# Geiger_Counter_II_2021-02-28.net
KiCad netlist of a schematic drawn in EasyEDA
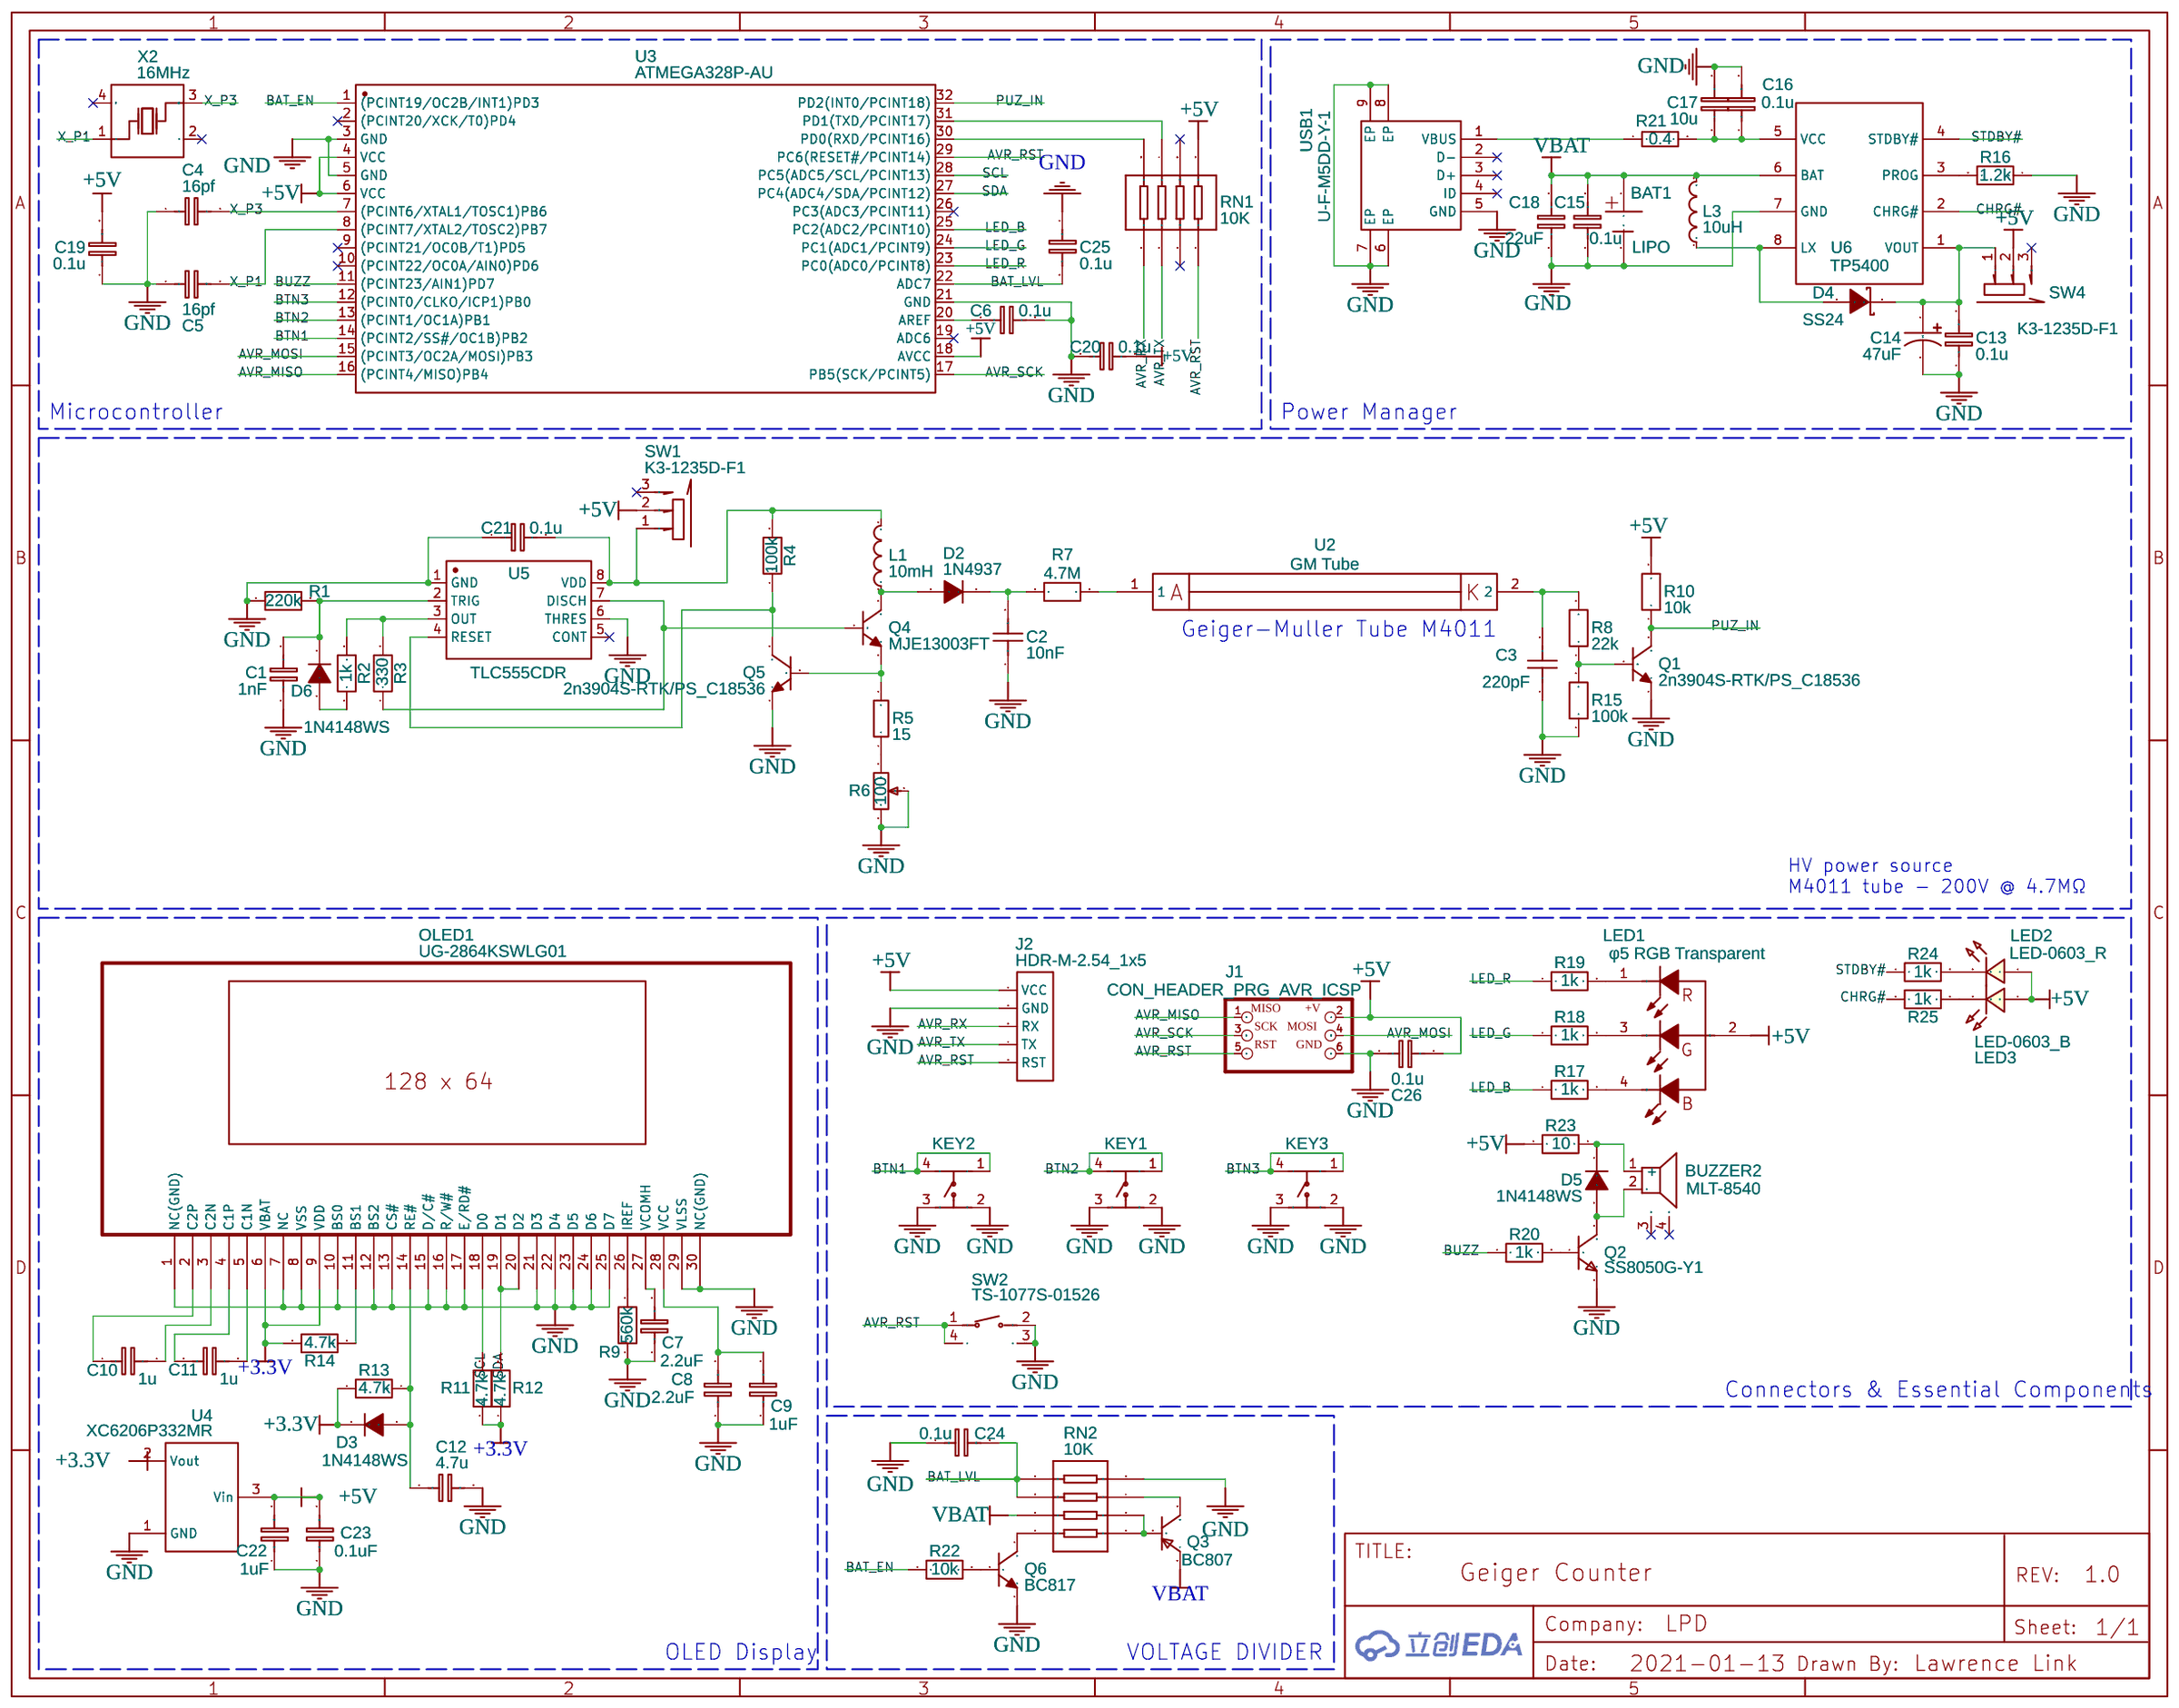
[diagram p0: schematic sheet]

(export (version "E")
  (design (tool "Eeschema 10.0.6"))
  (components
    (comp (ref "BAT1")
      (value "LIPO")
      (fields (field (name "BOM_Supplier Part") "C426276"))
      (libsource (lib "") (part "Lithum-Polymer"))
    )
    (comp (ref "BUZZER2")
      (value "MLT-8540")
      (fields (field (name "BOM_Supplier Part") "C95300"))
      (libsource (lib "") (part "MLT-8540"))
    )
    (comp (ref "C1") (value "1nF") (libsource (lib "") (part "C_0603_EU_9")))
    (comp (ref "C2")
      (value "10nF")
      (fields
        (field (name "BOM_Manufacturer Part") "KP103J2J0701")
        (field (name "BOM_Supplier Part") "C390071")
      )
      (libsource (lib "") (part "KP103J2J0701"))
    )
    (comp (ref "C3")
      (value "220pF")
      (fields
        (field (name "BOM_Manufacturer Part") "FM31X221K501ECG")
        (field (name "BOM_Supplier Part") "C382231")
      )
      (libsource (lib "") (part "FM31X221K501ECG"))
    )
    (comp (ref "C4") (value "16pf") (libsource (lib "") (part "C_0603_EU_1")))
    (comp (ref "C5") (value "16pf") (libsource (lib "") (part "C_0603_EU_11")))
    (comp (ref "C6") (value "0.1u") (libsource (lib "") (part "C_0603_EU_1")))
    (comp (ref "C7") (value "2.2uF") (libsource (lib "") (part "C_0603_EU_4")))
    (comp (ref "C8") (value "2.2uF") (libsource (lib "") (part "C_0603_EU_4")))
    (comp (ref "C9") (value "1uF") (libsource (lib "") (part "C_0603_EU_4")))
    (comp (ref "C10") (value "1u") (libsource (lib "") (part "C_0603_EU_3")))
    (comp (ref "C11") (value "1u") (libsource (lib "") (part "C_0603_EU_3")))
    (comp (ref "C12") (value "4.7u") (libsource (lib "") (part "C_0603_EU_7")))
    (comp (ref "C13") (value "0.1u") (libsource (lib "") (part "C_0603_EU")))
    (comp (ref "C14")
      (value "47uF")
      (fields
        (field (name "BOM_Manufacturer Part") "F920J476MBA")
        (field (name "BOM_Supplier Part") "C389937")
      )
      (libsource (lib "") (part "F920J476MBA"))
    )
    (comp (ref "C15") (value "0.1u") (libsource (lib "") (part "C_0603_EU")))
    (comp (ref "C16") (value "0.1u") (libsource (lib "") (part "C_0603_EU")))
    (comp (ref "C17") (value "10u") (libsource (lib "") (part "C_0603_EU_2")))
    (comp (ref "C18") (value "22uF") (libsource (lib "") (part "C_0603_EU")))
    (comp (ref "C19") (value "0.1u") (libsource (lib "") (part "C_0603_EU_2")))
    (comp (ref "C20") (value "0.1u") (libsource (lib "") (part "C_0603_EU_1")))
    (comp (ref "C21") (value "0.1u") (libsource (lib "") (part "C_0603_EU_8")))
    (comp (ref "C22") (value "1uF") (libsource (lib "") (part "C_0603_EU_10")))
    (comp (ref "C23") (value "0.1uF") (libsource (lib "") (part "C_0603_EU_10")))
    (comp (ref "C24") (value "0.1u") (libsource (lib "") (part "C_0603_EU_3")))
    (comp (ref "C25") (value "0.1u") (libsource (lib "") (part "C_0603_EU_5")))
    (comp (ref "C26") (value "0.1u") (libsource (lib "") (part "C_0603_EU_6")))
    (comp (ref "D2")
      (value "1N4937")
      (fields (field (name "BOM_Supplier Part") "C237246"))
      (libsource (lib "") (part "1N4937"))
    )
    (comp (ref "D3")
      (value "1N4148WS")
      (fields (field (name "BOM_Supplier Part") "C179718"))
      (libsource (lib "") (part "1N4148WS_1"))
    )
    (comp (ref "D4")
      (value "SS24")
      (fields (field (name "BOM_Supplier Part") "C50645"))
      (libsource (lib "") (part "SS24"))
    )
    (comp (ref "D5")
      (value "1N4148WS")
      (fields (field (name "BOM_Supplier Part") "C179718"))
      (libsource (lib "") (part "1N4148WS"))
    )
    (comp (ref "D6")
      (value "1N4148WS")
      (fields (field (name "BOM_Supplier Part") "C179718"))
      (libsource (lib "") (part "1N4148WS"))
    )
    (comp (ref "J1") (value "CON_HEADER_PRG_AVR_ICSP") (libsource (lib "") (part "CON_HEADER_PRG_AVR_ICSP")))
    (comp (ref "J2")
      (value "HDR-M-2.54_1x5")
      (fields (field (name "BOM_Supplier Part") "C358687"))
      (libsource (lib "") (part "HDR-M-2.54_1x5"))
    )
    (comp (ref "KEY1")
      (value "TL3301NF160QG/P010515")
      (fields (field (name "BOM_Supplier Part") "C273527"))
      (libsource (lib "") (part "TL3301NF160QG/P010515"))
    )
    (comp (ref "KEY2")
      (value "TL3301NF160QG/P010515")
      (fields (field (name "BOM_Supplier Part") "C273527"))
      (libsource (lib "") (part "TL3301NF160QG/P010515"))
    )
    (comp (ref "KEY3")
      (value "TL3301NF160QG/P010515")
      (fields (field (name "BOM_Supplier Part") "C273527"))
      (libsource (lib "") (part "TL3301NF160QG/P010515"))
    )
    (comp (ref "L1")
      (value "10mH")
      (fields
        (field (name "BOM_Manufacturer Part") "FNR6045S103KT")
        (field (name "BOM_Supplier Part") "C168108")
      )
      (libsource (lib "") (part "FNR6045S103KT"))
    )
    (comp (ref "L3")
      (value "10uH")
      (fields
        (field (name "BOM_Manufacturer Part") "CKCS6045-10uH/M")
        (field (name "BOM_Supplier Part") "C354632")
      )
      (libsource (lib "") (part "CKCS6045-10UH/M"))
    )
    (comp (ref "LED1")
      (value "φ5 RGB Transparent")
      (fields
        (field (name "BOM_Manufacturer Part") "φ5 RGB Transparent LED")
        (field (name "BOM_Supplier Part") "C32985")
      )
      (libsource (lib "") (part "φ5 RGB Transparent"))
    )
    (comp (ref "LED2")
      (value "LED-0603_R")
      (fields
        (field (name "BOM_Manufacturer Part") "19-217/R6C-AL1M2VY/3T")
        (field (name "BOM_Supplier Part") "C72044")
      )
      (libsource (lib "") (part "LED-0603_R"))
    )
    (comp (ref "LED3")
      (value "LED-0603_B")
      (fields
        (field (name "BOM_Manufacturer Part") "19-217/BHC-ZL1M2RY/3T")
        (field (name "BOM_Supplier Part") "C72041")
      )
      (libsource (lib "") (part "LED-0603_B"))
    )
    (comp (ref "OLED1")
      (value "UG-2864KSWLG01")
      (fields (field (name "BOM_Supplier Part") "C113322"))
      (libsource (lib "") (part "UG-2864KSWLG01"))
    )
    (comp (ref "Q1")
      (value "2n3904S-RTK/PS_C18536")
      (fields
        (field (name "BOM_Manufacturer Part") "2n3904S-RTK/PS")
        (field (name "BOM_Supplier Part") "C18536")
      )
      (libsource (lib "") (part "2n3904S-RTK/PS_C18536"))
    )
    (comp (ref "Q2")
      (value "SS8050G-Y1")
      (fields (field (name "BOM_Supplier Part") "C380930"))
      (libsource (lib "") (part "SS8050G-Y1"))
    )
    (comp (ref "Q3")
      (value "BC807")
      (fields (field (name "BOM_Supplier Part") "C466642"))
      (libsource (lib "") (part "BC807"))
    )
    (comp (ref "Q4")
      (value "MJE13003FT")
      (fields (field (name "BOM_Supplier Part") "C358520"))
      (libsource (lib "") (part "MJE13003FT"))
    )
    (comp (ref "Q5")
      (value "2n3904S-RTK/PS_C18536")
      (fields
        (field (name "BOM_Manufacturer Part") "2n3904S-RTK/PS")
        (field (name "BOM_Supplier Part") "C18536")
      )
      (libsource (lib "") (part "2n3904S-RTK/PS_C18536_1"))
    )
    (comp (ref "Q6")
      (value "BC817")
      (fields (field (name "BOM_Supplier Part") "C8589"))
      (libsource (lib "") (part "BC817"))
    )
    (comp (ref "R1") (value "220k") (libsource (lib "") (part "R_0603_EU")))
    (comp (ref "R2") (value "1k") (libsource (lib "") (part "R_0603_EU_1")))
    (comp (ref "R3") (value "330") (libsource (lib "") (part "R_0603_EU_1")))
    (comp (ref "R4") (value "100k") (libsource (lib "") (part "R_0603_EU_1")))
    (comp (ref "R5")
      (value "15")
      (fields
        (field (name "BOM_Manufacturer Part") "AR06BTDV0150")
        (field (name "BOM_Supplier Part") "C319834")
      )
      (libsource (lib "") (part "AR06BTDV0150"))
    )
    (comp (ref "R6")
      (value "100")
      (fields
        (field (name "BOM_Manufacturer Part") "3386P-1-101LF")
        (field (name "BOM_Supplier Part") "C125022")
      )
      (libsource (lib "") (part "3386P-1-101LF_EU"))
    )
    (comp (ref "R7") (value "4.7M") (libsource (lib "") (part "R_AXIAL-0.3_EU")))
    (comp (ref "R8") (value "22k") (libsource (lib "") (part "R_0805_EU_1")))
    (comp (ref "R9") (value "560k") (libsource (lib "") (part "R_0603_EU_1")))
    (comp (ref "R10") (value "10k") (libsource (lib "") (part "R_0805_EU_1")))
    (comp (ref "R11") (value "4.7k") (libsource (lib "") (part "R_0603_EU_1")))
    (comp (ref "R12") (value "4.7k") (libsource (lib "") (part "R_0603_EU_1")))
    (comp (ref "R13") (value "4.7k") (libsource (lib "") (part "R_0603_EU")))
    (comp (ref "R14") (value "4.7k") (libsource (lib "") (part "R_0603_EU_2")))
    (comp (ref "R15") (value "100k") (libsource (lib "") (part "R_0805_EU_1")))
    (comp (ref "R16") (value "1.2k") (libsource (lib "") (part "R_0603_EU")))
    (comp (ref "R17") (value "1k") (libsource (lib "") (part "R_0805_EU")))
    (comp (ref "R18") (value "1k") (libsource (lib "") (part "R_0805_EU")))
    (comp (ref "R19") (value "1k") (libsource (lib "") (part "R_0805_EU")))
    (comp (ref "R20") (value "1k") (libsource (lib "") (part "R_0603_EU_2")))
    (comp (ref "R21")
      (value "0.4")
      (fields
        (field (name "BOM_Manufacturer Part") "1206W4J040KT5E")
        (field (name "BOM_Supplier Part") "C620968")
      )
      (libsource (lib "") (part "1206W4J040KT5E"))
    )
    (comp (ref "R22") (value "10k") (libsource (lib "") (part "R_0603_EU_2")))
    (comp (ref "R23") (value "10") (libsource (lib "") (part "R_0603_EU_2")))
    (comp (ref "R24") (value "1k") (libsource (lib "") (part "R_0603_EU_2")))
    (comp (ref "R25") (value "1k") (libsource (lib "") (part "R_0603_EU_2")))
    (comp (ref "RN1")
      (value "10K")
      (fields
        (field (name "BOM_Manufacturer Part") "CN34JTN102")
        (field (name "BOM_Supplier Part") "C153136")
      )
      (libsource (lib "") (part "CN34JTN102"))
    )
    (comp (ref "RN2")
      (value "10K")
      (fields
        (field (name "BOM_Manufacturer Part") "4D03WGJ0103T5E")
        (field (name "BOM_Supplier Part") "C29718")
      )
      (libsource (lib "") (part "4D03WGJ0103T5E"))
    )
    (comp (ref "SW1")
      (value "K3-1235D-F1")
      (fields (field (name "BOM_Supplier Part") "C223839"))
      (libsource (lib "") (part "K3-1235D-F1"))
    )
    (comp (ref "SW2")
      (value "TS-1077S-01526")
      (fields (field (name "BOM_Supplier Part") "C455259"))
      (libsource (lib "") (part "TS-1077S-01526"))
    )
    (comp (ref "SW4")
      (value "K3-1235D-F1")
      (fields (field (name "BOM_Supplier Part") "C223839"))
      (libsource (lib "") (part "K3-1235D-F1_1"))
    )
    (comp (ref "U2") (value "GM Tube") (libsource (lib "") (part "GM Tube")))
    (comp (ref "U3")
      (value "ATMEGA328P-AU")
      (fields (field (name "BOM_Supplier Part") "C14877"))
      (libsource (lib "") (part "ATMEGA328P-AU"))
    )
    (comp (ref "U4")
      (value "XC6206P332MR")
      (fields (field (name "BOM_Supplier Part") "C5446"))
      (libsource (lib "") (part "XC6206P332MR"))
    )
    (comp (ref "U5")
      (value "TLC555CDR")
      (fields (field (name "BOM_Supplier Part") "C6986"))
      (libsource (lib "") (part "TLC555CDR"))
    )
    (comp (ref "U6")
      (value "TP5400")
      (fields (field (name "BOM_Supplier Part") "C24154"))
      (libsource (lib "") (part "TP5400"))
    )
    (comp (ref "USB1")
      (value "U-F-M5DD-Y-1")
      (fields (field (name "BOM_Supplier Part") "C91467"))
      (libsource (lib "") (part "U-F-M5DD-Y-1"))
    )
    (comp (ref "X2")
      (value "16MHz")
      (fields (field (name "BOM_Supplier Part") "C164049"))
      (libsource (lib "") (part "SMD-3225_4P 16MHz 20pF 10ppm -40&#126;+85℃"))
    )
  )
  (nets
    (net (code "1") (name "+3.3V") (class "Default")
      (node (ref "D3") (pin "1") (pinfunction "K_1") (pintype "unspecified"))
      (node (ref "OLED1") (pin "6") (pinfunction "VBAT_6") (pintype "passive"))
      (node (ref "OLED1") (pin "9") (pinfunction "VDD_9") (pintype "passive"))
      (node (ref "R11") (pin "1") (pinfunction "1_1") (pintype "unspecified"))
      (node (ref "R12") (pin "1") (pinfunction "1_1") (pintype "unspecified"))
      (node (ref "R13") (pin "2") (pinfunction "2_2") (pintype "unspecified"))
      (node (ref "R14") (pin "1") (pinfunction "1_1") (pintype "unspecified"))
      (node (ref "U4") (pin "2") (pinfunction "Vout_2") (pintype "unspecified"))
    )
    (net (code "2") (name "+5V") (class "Default")
      (node (ref "C19") (pin "2") (pinfunction "2_2") (pintype "unspecified"))
      (node (ref "C20") (pin "2") (pinfunction "2_2") (pintype "unspecified"))
      (node (ref "C22") (pin "2") (pinfunction "2_2") (pintype "unspecified"))
      (node (ref "C23") (pin "2") (pinfunction "2_2") (pintype "unspecified"))
      (node (ref "C26") (pin "2") (pinfunction "2_2") (pintype "unspecified"))
      (node (ref "J1") (pin "2") (pinfunction "+V_2") (pintype "unspecified"))
      (node (ref "J2") (pin "1") (pinfunction "VCC_1") (pintype "unspecified"))
      (node (ref "LED1") (pin "2") (pinfunction "CA_2") (pintype "unspecified"))
      (node (ref "LED2") (pin "1") (pinfunction "1_1") (pintype "unspecified"))
      (node (ref "LED3") (pin "1") (pinfunction "1_1") (pintype "unspecified"))
      (node (ref "R10") (pin "2") (pinfunction "2_2") (pintype "unspecified"))
      (node (ref "R23") (pin "1") (pinfunction "1_1") (pintype "unspecified"))
      (node (ref "RN1") (pin "5") (pinfunction "5_5") (pintype "input"))
      (node (ref "SW1") (pin "2") (pinfunction "2_2") (pintype "unspecified"))
      (node (ref "SW4") (pin "2") (pinfunction "2_2") (pintype "unspecified"))
      (node (ref "U3") (pin "18") (pinfunction "AVCC_18") (pintype "unspecified"))
      (node (ref "U3") (pin "4") (pinfunction "VCC_4") (pintype "unspecified"))
      (node (ref "U3") (pin "6") (pinfunction "VCC_6") (pintype "unspecified"))
      (node (ref "U4") (pin "3") (pinfunction "Vin_3") (pintype "unspecified"))
    )
    (net (code "3") (name "/AVR_MISO") (class "Default")
      (node (ref "J1") (pin "1") (pinfunction "MISO_1") (pintype "unspecified"))
      (node (ref "U3") (pin "16") (pinfunction "(PCINT4/MISO)PB4_16") (pintype "unspecified"))
    )
    (net (code "4") (name "/AVR_MOSI") (class "Default")
      (node (ref "J1") (pin "4") (pinfunction "MOSI_4") (pintype "unspecified"))
      (node (ref "U3") (pin "15") (pinfunction "(PCINT3/OC2A/MOSI)PB3_15") (pintype "unspecified"))
    )
    (net (code "5") (name "/AVR_RST") (class "Default")
      (node (ref "J1") (pin "5") (pinfunction "RST_5") (pintype "unspecified"))
      (node (ref "J2") (pin "5") (pinfunction "RST_5") (pintype "unspecified"))
      (node (ref "RN1") (pin "4") (pinfunction "4_4") (pintype "input"))
      (node (ref "SW2") (pin "1") (pinfunction "1_1") (pintype "unspecified"))
      (node (ref "SW2") (pin "4") (pinfunction "4_4") (pintype "unspecified"))
      (node (ref "U3") (pin "29") (pinfunction "PC6(RESET#/PCINT14)_29") (pintype "unspecified"))
    )
    (net (code "6") (name "/AVR_RX") (class "Default")
      (node (ref "J2") (pin "3") (pinfunction "RX_3") (pintype "unspecified"))
      (node (ref "RN1") (pin "1") (pinfunction "1_1") (pintype "input"))
    )
    (net (code "7") (name "/AVR_SCK") (class "Default")
      (node (ref "J1") (pin "3") (pinfunction "SCK_3") (pintype "unspecified"))
      (node (ref "U3") (pin "17") (pinfunction "PB5(SCK/PCINT5)_17") (pintype "unspecified"))
    )
    (net (code "8") (name "/AVR_TX") (class "Default")
      (node (ref "J2") (pin "4") (pinfunction "TX_4") (pintype "unspecified"))
      (node (ref "RN1") (pin "2") (pinfunction "2_2") (pintype "input"))
    )
    (net (code "9") (name "/BAT_EN") (class "Default")
      (node (ref "R22") (pin "1") (pinfunction "1_1") (pintype "unspecified"))
      (node (ref "U3") (pin "1") (pinfunction "(PCINT19/OC2B/INT1)PD3_1") (pintype "unspecified"))
    )
    (net (code "10") (name "/BAT_LVL") (class "Default")
      (node (ref "C24") (pin "2") (pinfunction "2_2") (pintype "unspecified"))
      (node (ref "C25") (pin "2") (pinfunction "2_2") (pintype "unspecified"))
      (node (ref "RN2") (pin "1") (pinfunction "1_1") (pintype "input"))
      (node (ref "RN2") (pin "2") (pinfunction "2_2") (pintype "input"))
      (node (ref "U3") (pin "22") (pinfunction "ADC7_22") (pintype "unspecified"))
    )
    (net (code "11") (name "/BTN1") (class "Default")
      (node (ref "KEY2") (pin "1") (pinfunction "3_1") (pintype "unspecified"))
      (node (ref "KEY2") (pin "4") (pinfunction "4_4") (pintype "unspecified"))
      (node (ref "U3") (pin "14") (pinfunction "(PCINT2/SS#/OC1B)PB2_14") (pintype "unspecified"))
    )
    (net (code "12") (name "/BTN2") (class "Default")
      (node (ref "KEY1") (pin "1") (pinfunction "3_1") (pintype "unspecified"))
      (node (ref "KEY1") (pin "4") (pinfunction "4_4") (pintype "unspecified"))
      (node (ref "U3") (pin "13") (pinfunction "(PCINT1/OC1A)PB1_13") (pintype "unspecified"))
    )
    (net (code "13") (name "/BTN3") (class "Default")
      (node (ref "KEY3") (pin "1") (pinfunction "3_1") (pintype "unspecified"))
      (node (ref "KEY3") (pin "4") (pinfunction "4_4") (pintype "unspecified"))
      (node (ref "U3") (pin "12") (pinfunction "(PCINT0/CLKO/ICP1)PB0_12") (pintype "unspecified"))
    )
    (net (code "14") (name "/BUZZ") (class "Default")
      (node (ref "R20") (pin "1") (pinfunction "1_1") (pintype "unspecified"))
      (node (ref "U3") (pin "11") (pinfunction "(PCINT23/AIN1)PD7_11") (pintype "unspecified"))
    )
    (net (code "15") (name "/CHRG#") (class "Default")
      (node (ref "R25") (pin "1") (pinfunction "1_1") (pintype "unspecified"))
      (node (ref "U6") (pin "2") (pinfunction "CHRG#_2") (pintype "unspecified"))
    )
    (net (code "16") (name "/LED_B") (class "Default")
      (node (ref "R17") (pin "1") (pinfunction "1_1") (pintype "unspecified"))
      (node (ref "U3") (pin "25") (pinfunction "PC2(ADC2/PCINT10)_25") (pintype "unspecified"))
    )
    (net (code "17") (name "/LED_G") (class "Default")
      (node (ref "R18") (pin "1") (pinfunction "1_1") (pintype "unspecified"))
      (node (ref "U3") (pin "24") (pinfunction "PC1(ADC1/PCINT9)_24") (pintype "unspecified"))
    )
    (net (code "18") (name "/LED_R") (class "Default")
      (node (ref "R19") (pin "1") (pinfunction "1_1") (pintype "unspecified"))
      (node (ref "U3") (pin "23") (pinfunction "PC0(ADC0/PCINT8)_23") (pintype "unspecified"))
    )
    (net (code "19") (name "/PUZ_IN") (class "Default")
      (node (ref "Q1") (pin "3") (pinfunction "C_3") (pintype "input"))
      (node (ref "R10") (pin "1") (pinfunction "1_1") (pintype "unspecified"))
      (node (ref "U3") (pin "32") (pinfunction "PD2(INT0/PCINT18)_32") (pintype "unspecified"))
    )
    (net (code "20") (name "/SCL") (class "Default")
      (node (ref "OLED1") (pin "18") (pinfunction "D0_18") (pintype "passive"))
      (node (ref "R11") (pin "2") (pinfunction "2_2") (pintype "unspecified"))
      (node (ref "U3") (pin "28") (pinfunction "PC5(ADC5/SCL/PCINT13)_28") (pintype "unspecified"))
    )
    (net (code "21") (name "/SDA") (class "Default")
      (node (ref "OLED1") (pin "19") (pinfunction "D1_19") (pintype "passive"))
      (node (ref "OLED1") (pin "20") (pinfunction "D2_20") (pintype "passive"))
      (node (ref "R12") (pin "2") (pinfunction "2_2") (pintype "unspecified"))
      (node (ref "U3") (pin "27") (pinfunction "PC4(ADC4/SDA/PCINT12)_27") (pintype "unspecified"))
    )
    (net (code "22") (name "/STDBY#") (class "Default")
      (node (ref "R24") (pin "1") (pinfunction "1_1") (pintype "unspecified"))
      (node (ref "U6") (pin "4") (pinfunction "STDBY#_4") (pintype "unspecified"))
    )
    (net (code "23") (name "/X_P1") (class "Default")
      (node (ref "C5") (pin "2") (pinfunction "2_2") (pintype "unspecified"))
      (node (ref "U3") (pin "8") (pinfunction "(PCINT7/XTAL2/TOSC2)PB7_8") (pintype "unspecified"))
      (node (ref "X2") (pin "1") (pinfunction "OSC1_1") (pintype "unspecified"))
    )
    (net (code "24") (name "/X_P3") (class "Default")
      (node (ref "C4") (pin "2") (pinfunction "2_2") (pintype "unspecified"))
      (node (ref "U3") (pin "7") (pinfunction "(PCINT6/XTAL1/TOSC1)PB6_7") (pintype "unspecified"))
      (node (ref "X2") (pin "3") (pinfunction "OSC2_3") (pintype "unspecified"))
    )
    (net (code "25") (name "GND") (class "Default")
      (node (ref "BAT1") (pin "2") (pinfunction "2_2") (pintype "unspecified"))
      (node (ref "C1") (pin "1") (pinfunction "1_1") (pintype "unspecified"))
      (node (ref "C12") (pin "2") (pinfunction "2_2") (pintype "unspecified"))
      (node (ref "C13") (pin "1") (pinfunction "1_1") (pintype "unspecified"))
      (node (ref "C14") (pin "2") (pinfunction "2_2") (pintype "unspecified"))
      (node (ref "C15") (pin "1") (pinfunction "1_1") (pintype "unspecified"))
      (node (ref "C16") (pin "2") (pinfunction "2_2") (pintype "unspecified"))
      (node (ref "C17") (pin "2") (pinfunction "2_2") (pintype "unspecified"))
      (node (ref "C18") (pin "1") (pinfunction "1_1") (pintype "unspecified"))
      (node (ref "C19") (pin "1") (pinfunction "1_1") (pintype "unspecified"))
      (node (ref "C2") (pin "1") (pinfunction "1_1") (pintype "unspecified"))
      (node (ref "C20") (pin "1") (pinfunction "1_1") (pintype "unspecified"))
      (node (ref "C21") (pin "1") (pinfunction "1_1") (pintype "unspecified"))
      (node (ref "C22") (pin "1") (pinfunction "1_1") (pintype "unspecified"))
      (node (ref "C23") (pin "1") (pinfunction "1_1") (pintype "unspecified"))
      (node (ref "C24") (pin "1") (pinfunction "1_1") (pintype "unspecified"))
      (node (ref "C25") (pin "1") (pinfunction "1_1") (pintype "unspecified"))
      (node (ref "C26") (pin "1") (pinfunction "1_1") (pintype "unspecified"))
      (node (ref "C3") (pin "1") (pinfunction "1_1") (pintype "unspecified"))
      (node (ref "C4") (pin "1") (pinfunction "1_1") (pintype "unspecified"))
      (node (ref "C5") (pin "1") (pinfunction "1_1") (pintype "unspecified"))
      (node (ref "C6") (pin "2") (pinfunction "2_2") (pintype "unspecified"))
      (node (ref "C7") (pin "1") (pinfunction "1_1") (pintype "unspecified"))
      (node (ref "C8") (pin "1") (pinfunction "1_1") (pintype "unspecified"))
      (node (ref "C9") (pin "1") (pinfunction "1_1") (pintype "unspecified"))
      (node (ref "J1") (pin "6") (pinfunction "GND_6") (pintype "unspecified"))
      (node (ref "J2") (pin "2") (pinfunction "GND_2") (pintype "unspecified"))
      (node (ref "KEY1") (pin "2") (pinfunction "2_2") (pintype "unspecified"))
      (node (ref "KEY1") (pin "3") (pinfunction "1_3") (pintype "unspecified"))
      (node (ref "KEY2") (pin "2") (pinfunction "2_2") (pintype "unspecified"))
      (node (ref "KEY2") (pin "3") (pinfunction "1_3") (pintype "unspecified"))
      (node (ref "KEY3") (pin "2") (pinfunction "2_2") (pintype "unspecified"))
      (node (ref "KEY3") (pin "3") (pinfunction "1_3") (pintype "unspecified"))
      (node (ref "OLED1") (pin "1") (pinfunction "NC(GND)_1") (pintype "passive"))
      (node (ref "OLED1") (pin "10") (pinfunction "BS0_10") (pintype "passive"))
      (node (ref "OLED1") (pin "12") (pinfunction "BS2_12") (pintype "passive"))
      (node (ref "OLED1") (pin "13") (pinfunction "CS#_13") (pintype "passive"))
      (node (ref "OLED1") (pin "15") (pinfunction "D/C#_15") (pintype "passive"))
      (node (ref "OLED1") (pin "16") (pinfunction "R/W#_16") (pintype "passive"))
      (node (ref "OLED1") (pin "17") (pinfunction "E/RD#_17") (pintype "passive"))
      (node (ref "OLED1") (pin "21") (pinfunction "D3_21") (pintype "passive"))
      (node (ref "OLED1") (pin "22") (pinfunction "D4_22") (pintype "passive"))
      (node (ref "OLED1") (pin "23") (pinfunction "D5_23") (pintype "passive"))
      (node (ref "OLED1") (pin "24") (pinfunction "D6_24") (pintype "passive"))
      (node (ref "OLED1") (pin "25") (pinfunction "D7_25") (pintype "passive"))
      (node (ref "OLED1") (pin "29") (pinfunction "VLSS_29") (pintype "passive"))
      (node (ref "OLED1") (pin "30") (pinfunction "NC(GND)_30") (pintype "passive"))
      (node (ref "OLED1") (pin "7") (pinfunction "NC_7") (pintype "passive"))
      (node (ref "OLED1") (pin "8") (pinfunction "VSS_8") (pintype "passive"))
      (node (ref "Q1") (pin "1") (pinfunction "E_1") (pintype "input"))
      (node (ref "Q2") (pin "2") (pinfunction "E_2") (pintype "unspecified"))
      (node (ref "Q5") (pin "1") (pinfunction "E_1") (pintype "input"))
      (node (ref "Q6") (pin "2") (pinfunction "E_2") (pintype "unspecified"))
      (node (ref "R1") (pin "2") (pinfunction "2_2") (pintype "unspecified"))
      (node (ref "R15") (pin "1") (pinfunction "1_1") (pintype "unspecified"))
      (node (ref "R16") (pin "1") (pinfunction "1_1") (pintype "unspecified"))
      (node (ref "R6") (pin "2") (pinfunction "2_2") (pintype "input"))
      (node (ref "R6") (pin "3") (pinfunction "3_3") (pintype "input"))
      (node (ref "R9") (pin "1") (pinfunction "1_1") (pintype "unspecified"))
      (node (ref "RN2") (pin "8") (pinfunction "8_8") (pintype "input"))
      (node (ref "SW2") (pin "2") (pinfunction "2_2") (pintype "unspecified"))
      (node (ref "SW2") (pin "3") (pinfunction "3_3") (pintype "unspecified"))
      (node (ref "U3") (pin "21") (pinfunction "GND_21") (pintype "unspecified"))
      (node (ref "U3") (pin "3") (pinfunction "GND_3") (pintype "unspecified"))
      (node (ref "U3") (pin "5") (pinfunction "GND_5") (pintype "unspecified"))
      (node (ref "U4") (pin "1") (pinfunction "GND_1") (pintype "unspecified"))
      (node (ref "U5") (pin "1") (pinfunction "GND_1") (pintype "unspecified"))
      (node (ref "U5") (pin "6") (pinfunction "THRES_6") (pintype "unspecified"))
      (node (ref "U6") (pin "7") (pinfunction "GND_7") (pintype "unspecified"))
      (node (ref "USB1") (pin "5") (pinfunction "GND_5") (pintype "unspecified"))
      (node (ref "USB1") (pin "6") (pinfunction "EP_6") (pintype "unspecified"))
      (node (ref "USB1") (pin "7") (pinfunction "EP_7") (pintype "unspecified"))
      (node (ref "USB1") (pin "8") (pinfunction "EP_8") (pintype "unspecified"))
      (node (ref "USB1") (pin "9") (pinfunction "EP_9") (pintype "unspecified"))
    )
    (net (code "26") (name "Net-(BUZZER2-+)") (class "Default")
      (node (ref "BUZZER2") (pin "1") (pinfunction "+_1") (pintype "unspecified"))
      (node (ref "D5") (pin "1") (pinfunction "K_1") (pintype "unspecified"))
      (node (ref "R23") (pin "2") (pinfunction "2_2") (pintype "unspecified"))
    )
    (net (code "27") (name "Net-(C3-Pad2)") (class "Default")
      (node (ref "C3") (pin "2") (pinfunction "2_2") (pintype "unspecified"))
      (node (ref "R8") (pin "2") (pinfunction "2_2") (pintype "unspecified"))
      (node (ref "U2") (pin "2") (pinfunction "2_2") (pintype "unspecified"))
    )
    (net (code "28") (name "Net-(D2-A)") (class "Default")
      (node (ref "D2") (pin "2") (pinfunction "A_2") (pintype "unspecified"))
      (node (ref "L1") (pin "1") (pinfunction "1_1") (pintype "unspecified"))
      (node (ref "Q4") (pin "2") (pinfunction "C_2") (pintype "unspecified"))
    )
    (net (code "29") (name "Net-(D2-K)") (class "Default")
      (node (ref "C2") (pin "2") (pinfunction "2_2") (pintype "unspecified"))
      (node (ref "D2") (pin "1") (pinfunction "K_1") (pintype "unspecified"))
      (node (ref "R7") (pin "1") (pinfunction "1_1") (pintype "unspecified"))
    )
    (net (code "30") (name "Net-(D3-A)") (class "Default")
      (node (ref "C12") (pin "1") (pinfunction "1_1") (pintype "unspecified"))
      (node (ref "D3") (pin "2") (pinfunction "A_2") (pintype "unspecified"))
      (node (ref "OLED1") (pin "14") (pinfunction "RE#_14") (pintype "passive"))
      (node (ref "R13") (pin "1") (pinfunction "1_1") (pintype "unspecified"))
    )
    (net (code "31") (name "Net-(D4-A)") (class "Default")
      (node (ref "D4") (pin "2") (pinfunction "A_2") (pintype "unspecified"))
      (node (ref "L3") (pin "1") (pinfunction "1_1") (pintype "unspecified"))
      (node (ref "U6") (pin "8") (pinfunction "LX_8") (pintype "unspecified"))
    )
    (net (code "32") (name "Net-(D4-K)") (class "Default")
      (node (ref "C13") (pin "2") (pinfunction "2_2") (pintype "unspecified"))
      (node (ref "C14") (pin "1") (pinfunction "1_1") (pintype "unspecified"))
      (node (ref "D4") (pin "1") (pinfunction "K_1") (pintype "unspecified"))
      (node (ref "SW4") (pin "1") (pinfunction "1_1") (pintype "unspecified"))
      (node (ref "U6") (pin "1") (pinfunction "VOUT_1") (pintype "unspecified"))
    )
    (net (code "33") (name "Net-(D5-A)") (class "Default")
      (node (ref "BUZZER2") (pin "2") (pinfunction "2_2") (pintype "unspecified"))
      (node (ref "D5") (pin "2") (pinfunction "A_2") (pintype "unspecified"))
      (node (ref "Q2") (pin "3") (pinfunction "C_3") (pintype "unspecified"))
    )
    (net (code "34") (name "Net-(D6-A)") (class "Default")
      (node (ref "D6") (pin "2") (pinfunction "A_2") (pintype "unspecified"))
      (node (ref "R2") (pin "1") (pinfunction "1_1") (pintype "unspecified"))
    )
    (net (code "35") (name "Net-(D6-K)") (class "Default")
      (node (ref "C1") (pin "2") (pinfunction "2_2") (pintype "unspecified"))
      (node (ref "D6") (pin "1") (pinfunction "K_1") (pintype "unspecified"))
      (node (ref "R1") (pin "1") (pinfunction "1_1") (pintype "unspecified"))
      (node (ref "U5") (pin "2") (pinfunction "TRIG_2") (pintype "unspecified"))
    )
    (net (code "36") (name "Net-(LED1-KB)") (class "Default")
      (node (ref "LED1") (pin "4") (pinfunction "KB_4") (pintype "unspecified"))
      (node (ref "R17") (pin "2") (pinfunction "2_2") (pintype "unspecified"))
    )
    (net (code "37") (name "Net-(LED1-KG)") (class "Default")
      (node (ref "LED1") (pin "3") (pinfunction "KG_3") (pintype "unspecified"))
      (node (ref "R18") (pin "2") (pinfunction "2_2") (pintype "unspecified"))
    )
    (net (code "38") (name "Net-(LED1-KR)") (class "Default")
      (node (ref "LED1") (pin "1") (pinfunction "KR_1") (pintype "unspecified"))
      (node (ref "R19") (pin "2") (pinfunction "2_2") (pintype "unspecified"))
    )
    (net (code "39") (name "Net-(LED2-Pad2)") (class "Default")
      (node (ref "LED2") (pin "2") (pinfunction "2_2") (pintype "unspecified"))
      (node (ref "R24") (pin "2") (pinfunction "2_2") (pintype "unspecified"))
    )
    (net (code "40") (name "Net-(LED3-Pad2)") (class "Default")
      (node (ref "LED3") (pin "2") (pinfunction "2_2") (pintype "unspecified"))
      (node (ref "R25") (pin "2") (pinfunction "2_2") (pintype "unspecified"))
    )
    (net (code "41") (name "Net-(OLED1-BS1)") (class "Default")
      (node (ref "OLED1") (pin "11") (pinfunction "BS1_11") (pintype "passive"))
      (node (ref "R14") (pin "2") (pinfunction "2_2") (pintype "unspecified"))
    )
    (net (code "42") (name "Net-(OLED1-C1N)") (class "Default")
      (node (ref "C11") (pin "2") (pinfunction "2_2") (pintype "unspecified"))
      (node (ref "OLED1") (pin "5") (pinfunction "C1N_5") (pintype "passive"))
    )
    (net (code "43") (name "Net-(OLED1-C1P)") (class "Default")
      (node (ref "C11") (pin "1") (pinfunction "1_1") (pintype "unspecified"))
      (node (ref "OLED1") (pin "4") (pinfunction "C1P_4") (pintype "passive"))
    )
    (net (code "44") (name "Net-(OLED1-C2N)") (class "Default")
      (node (ref "C10") (pin "2") (pinfunction "2_2") (pintype "unspecified"))
      (node (ref "OLED1") (pin "3") (pinfunction "C2N_3") (pintype "passive"))
    )
    (net (code "45") (name "Net-(OLED1-C2P)") (class "Default")
      (node (ref "C10") (pin "1") (pinfunction "1_1") (pintype "unspecified"))
      (node (ref "OLED1") (pin "2") (pinfunction "C2P_2") (pintype "passive"))
    )
    (net (code "46") (name "Net-(OLED1-IREF)") (class "Default")
      (node (ref "OLED1") (pin "26") (pinfunction "IREF_26") (pintype "passive"))
      (node (ref "R9") (pin "2") (pinfunction "2_2") (pintype "unspecified"))
    )
    (net (code "47") (name "Net-(OLED1-VCC)") (class "Default")
      (node (ref "C8") (pin "2") (pinfunction "2_2") (pintype "unspecified"))
      (node (ref "C9") (pin "2") (pinfunction "2_2") (pintype "unspecified"))
      (node (ref "OLED1") (pin "28") (pinfunction "VCC_28") (pintype "passive"))
    )
    (net (code "48") (name "Net-(OLED1-VCOMH)") (class "Default")
      (node (ref "C7") (pin "2") (pinfunction "2_2") (pintype "unspecified"))
      (node (ref "OLED1") (pin "27") (pinfunction "VCOMH_27") (pintype "passive"))
    )
    (net (code "49") (name "Net-(Q1-B)") (class "Default")
      (node (ref "Q1") (pin "2") (pinfunction "B_2") (pintype "input"))
      (node (ref "R15") (pin "2") (pinfunction "2_2") (pintype "unspecified"))
      (node (ref "R8") (pin "1") (pinfunction "1_1") (pintype "unspecified"))
    )
    (net (code "50") (name "Net-(Q2-B)") (class "Default")
      (node (ref "Q2") (pin "1") (pinfunction "B_1") (pintype "unspecified"))
      (node (ref "R20") (pin "2") (pinfunction "2_2") (pintype "unspecified"))
    )
    (net (code "51") (name "Net-(Q3-B)") (class "Default")
      (node (ref "Q3") (pin "1") (pinfunction "B_1") (pintype "unspecified"))
      (node (ref "RN2") (pin "5") (pinfunction "5_5") (pintype "input"))
      (node (ref "RN2") (pin "6") (pinfunction "6_6") (pintype "input"))
    )
    (net (code "52") (name "Net-(Q3-C)") (class "Default")
      (node (ref "Q3") (pin "3") (pinfunction "C_3") (pintype "unspecified"))
      (node (ref "RN2") (pin "7") (pinfunction "7_7") (pintype "input"))
    )
    (net (code "53") (name "Net-(Q4-B)") (class "Default")
      (node (ref "Q4") (pin "1") (pinfunction "B_1") (pintype "unspecified"))
      (node (ref "R3") (pin "1") (pinfunction "1_1") (pintype "unspecified"))
      (node (ref "U5") (pin "7") (pinfunction "DISCH_7") (pintype "unspecified"))
    )
    (net (code "54") (name "Net-(Q4-E)") (class "Default")
      (node (ref "Q4") (pin "3") (pinfunction "E_3") (pintype "unspecified"))
      (node (ref "Q5") (pin "2") (pinfunction "B_2") (pintype "input"))
      (node (ref "R5") (pin "2") (pinfunction "2_2") (pintype "unspecified"))
    )
    (net (code "55") (name "Net-(Q5-C)") (class "Default")
      (node (ref "Q5") (pin "3") (pinfunction "C_3") (pintype "input"))
      (node (ref "R4") (pin "1") (pinfunction "1_1") (pintype "unspecified"))
      (node (ref "U5") (pin "4") (pinfunction "RESET_4") (pintype "unspecified"))
    )
    (net (code "56") (name "Net-(Q6-B)") (class "Default")
      (node (ref "Q6") (pin "1") (pinfunction "B_1") (pintype "unspecified"))
      (node (ref "R22") (pin "2") (pinfunction "2_2") (pintype "unspecified"))
    )
    (net (code "57") (name "Net-(Q6-C)") (class "Default")
      (node (ref "Q6") (pin "3") (pinfunction "C_3") (pintype "unspecified"))
      (node (ref "RN2") (pin "4") (pinfunction "4_4") (pintype "input"))
    )
    (net (code "58") (name "Net-(R5-Pad1)") (class "Default")
      (node (ref "R5") (pin "1") (pinfunction "1_1") (pintype "unspecified"))
      (node (ref "R6") (pin "1") (pinfunction "1_1") (pintype "input"))
    )
    (net (code "59") (name "Net-(R7-Pad2)") (class "Default")
      (node (ref "R7") (pin "2") (pinfunction "2_2") (pintype "unspecified"))
      (node (ref "U2") (pin "1") (pinfunction "1_1") (pintype "unspecified"))
    )
    (net (code "60") (name "Net-(U3-AREF)") (class "Default")
      (node (ref "C6") (pin "1") (pinfunction "1_1") (pintype "unspecified"))
      (node (ref "U3") (pin "20") (pinfunction "AREF_20") (pintype "unspecified"))
    )
    (net (code "61") (name "Net-(U3-PD0(RXD{slash}PCINT16))") (class "Default")
      (node (ref "RN1") (pin "8") (pinfunction "8_8") (pintype "input"))
      (node (ref "U3") (pin "30") (pinfunction "PD0(RXD/PCINT16)_30") (pintype "unspecified"))
    )
    (net (code "62") (name "Net-(U3-PD1(TXD{slash}PCINT17))") (class "Default")
      (node (ref "RN1") (pin "7") (pinfunction "7_7") (pintype "input"))
      (node (ref "U3") (pin "31") (pinfunction "PD1(TXD/PCINT17)_31") (pintype "unspecified"))
    )
    (net (code "63") (name "Net-(U5-OUT)") (class "Default")
      (node (ref "R2") (pin "2") (pinfunction "2_2") (pintype "unspecified"))
      (node (ref "R3") (pin "2") (pinfunction "2_2") (pintype "unspecified"))
      (node (ref "U5") (pin "3") (pinfunction "OUT_3") (pintype "unspecified"))
    )
    (net (code "64") (name "Net-(U5-VDD)") (class "Default")
      (node (ref "C21") (pin "2") (pinfunction "2_2") (pintype "unspecified"))
      (node (ref "L1") (pin "2") (pinfunction "2_2") (pintype "unspecified"))
      (node (ref "R4") (pin "2") (pinfunction "2_2") (pintype "unspecified"))
      (node (ref "SW1") (pin "1") (pinfunction "1_1") (pintype "unspecified"))
      (node (ref "U5") (pin "8") (pinfunction "VDD_8") (pintype "unspecified"))
    )
    (net (code "65") (name "Net-(U6-PROG)") (class "Default")
      (node (ref "R16") (pin "2") (pinfunction "2_2") (pintype "unspecified"))
      (node (ref "U6") (pin "3") (pinfunction "PROG_3") (pintype "unspecified"))
    )
    (net (code "66") (name "Net-(U6-VCC)") (class "Default")
      (node (ref "C16") (pin "1") (pinfunction "1_1") (pintype "unspecified"))
      (node (ref "C17") (pin "1") (pinfunction "1_1") (pintype "unspecified"))
      (node (ref "R21") (pin "2") (pinfunction "2_2") (pintype "input"))
      (node (ref "U6") (pin "5") (pinfunction "VCC_5") (pintype "unspecified"))
    )
    (net (code "67") (name "Net-(USB1-VBUS)") (class "Default")
      (node (ref "R21") (pin "1") (pinfunction "1_1") (pintype "input"))
      (node (ref "USB1") (pin "1") (pinfunction "VBUS_1") (pintype "unspecified"))
    )
    (net (code "68") (name "VBAT") (class "Default")
      (node (ref "BAT1") (pin "1") (pinfunction "1_1") (pintype "unspecified"))
      (node (ref "C15") (pin "2") (pinfunction "2_2") (pintype "unspecified"))
      (node (ref "C18") (pin "2") (pinfunction "2_2") (pintype "unspecified"))
      (node (ref "L3") (pin "2") (pinfunction "2_2") (pintype "unspecified"))
      (node (ref "Q3") (pin "2") (pinfunction "E_2") (pintype "unspecified"))
      (node (ref "RN2") (pin "3") (pinfunction "3_3") (pintype "input"))
      (node (ref "U6") (pin "6") (pinfunction "BAT_6") (pintype "unspecified"))
    )
    (net (code "69") (name "unconnected-(BUZZER2-NC-Pad3)") (class "Default")
      (node (ref "BUZZER2") (pin "3") (pinfunction "NC_3") (pintype "unspecified+no_connect"))
    )
    (net (code "70") (name "unconnected-(BUZZER2-NC-Pad4)") (class "Default")
      (node (ref "BUZZER2") (pin "4") (pinfunction "NC_4") (pintype "unspecified+no_connect"))
    )
    (net (code "71") (name "unconnected-(RN1-Pad3)") (class "Default")
      (node (ref "RN1") (pin "3") (pinfunction "3_3") (pintype "input+no_connect"))
    )
    (net (code "72") (name "unconnected-(RN1-Pad6)") (class "Default")
      (node (ref "RN1") (pin "6") (pinfunction "6_6") (pintype "input+no_connect"))
    )
    (net (code "73") (name "unconnected-(SW1-Pad3)") (class "Default")
      (node (ref "SW1") (pin "3") (pinfunction "3_3") (pintype "unspecified+no_connect"))
    )
    (net (code "74") (name "unconnected-(SW4-Pad3)") (class "Default")
      (node (ref "SW4") (pin "3") (pinfunction "3_3") (pintype "unspecified+no_connect"))
    )
    (net (code "75") (name "unconnected-(U3-(PCINT20{slash}XCK{slash}T0)PD4-Pad2)") (class "Default")
      (node (ref "U3") (pin "2") (pinfunction "(PCINT20/XCK/T0)PD4_2") (pintype "unspecified+no_connect"))
    )
    (net (code "76") (name "unconnected-(U3-(PCINT21{slash}OC0B{slash}T1)PD5-Pad9)") (class "Default")
      (node (ref "U3") (pin "9") (pinfunction "(PCINT21/OC0B/T1)PD5_9") (pintype "unspecified+no_connect"))
    )
    (net (code "77") (name "unconnected-(U3-(PCINT22{slash}OC0A{slash}AIN0)PD6-Pad10)") (class "Default")
      (node (ref "U3") (pin "10") (pinfunction "(PCINT22/OC0A/AIN0)PD6_10") (pintype "unspecified+no_connect"))
    )
    (net (code "78") (name "unconnected-(U3-ADC6-Pad19)") (class "Default")
      (node (ref "U3") (pin "19") (pinfunction "ADC6_19") (pintype "unspecified+no_connect"))
    )
    (net (code "79") (name "unconnected-(U3-PC3(ADC3{slash}PCINT11)-Pad26)") (class "Default")
      (node (ref "U3") (pin "26") (pinfunction "PC3(ADC3/PCINT11)_26") (pintype "unspecified+no_connect"))
    )
    (net (code "80") (name "unconnected-(U5-CONT-Pad5)") (class "Default")
      (node (ref "U5") (pin "5") (pinfunction "CONT_5") (pintype "unspecified+no_connect"))
    )
    (net (code "81") (name "unconnected-(USB1-D+-Pad3)") (class "Default")
      (node (ref "USB1") (pin "3") (pinfunction "D+_3") (pintype "unspecified+no_connect"))
    )
    (net (code "82") (name "unconnected-(USB1-D--Pad2)") (class "Default")
      (node (ref "USB1") (pin "2") (pinfunction "D-_2") (pintype "unspecified+no_connect"))
    )
    (net (code "83") (name "unconnected-(USB1-ID-Pad4)") (class "Default")
      (node (ref "USB1") (pin "4") (pinfunction "ID_4") (pintype "unspecified+no_connect"))
    )
    (net (code "84") (name "unconnected-(X2-GND-Pad2)") (class "Default")
      (node (ref "X2") (pin "2") (pinfunction "GND_2") (pintype "unspecified+no_connect"))
    )
    (net (code "85") (name "unconnected-(X2-GND-Pad4)") (class "Default")
      (node (ref "X2") (pin "4") (pinfunction "GND_4") (pintype "unspecified+no_connect"))
    )
  )
)
